# HydraBus_1_0_Shield_ESP_WROOM_32_v1_1_Re.net
KiCad netlist of a schematic drawn in EAGLE
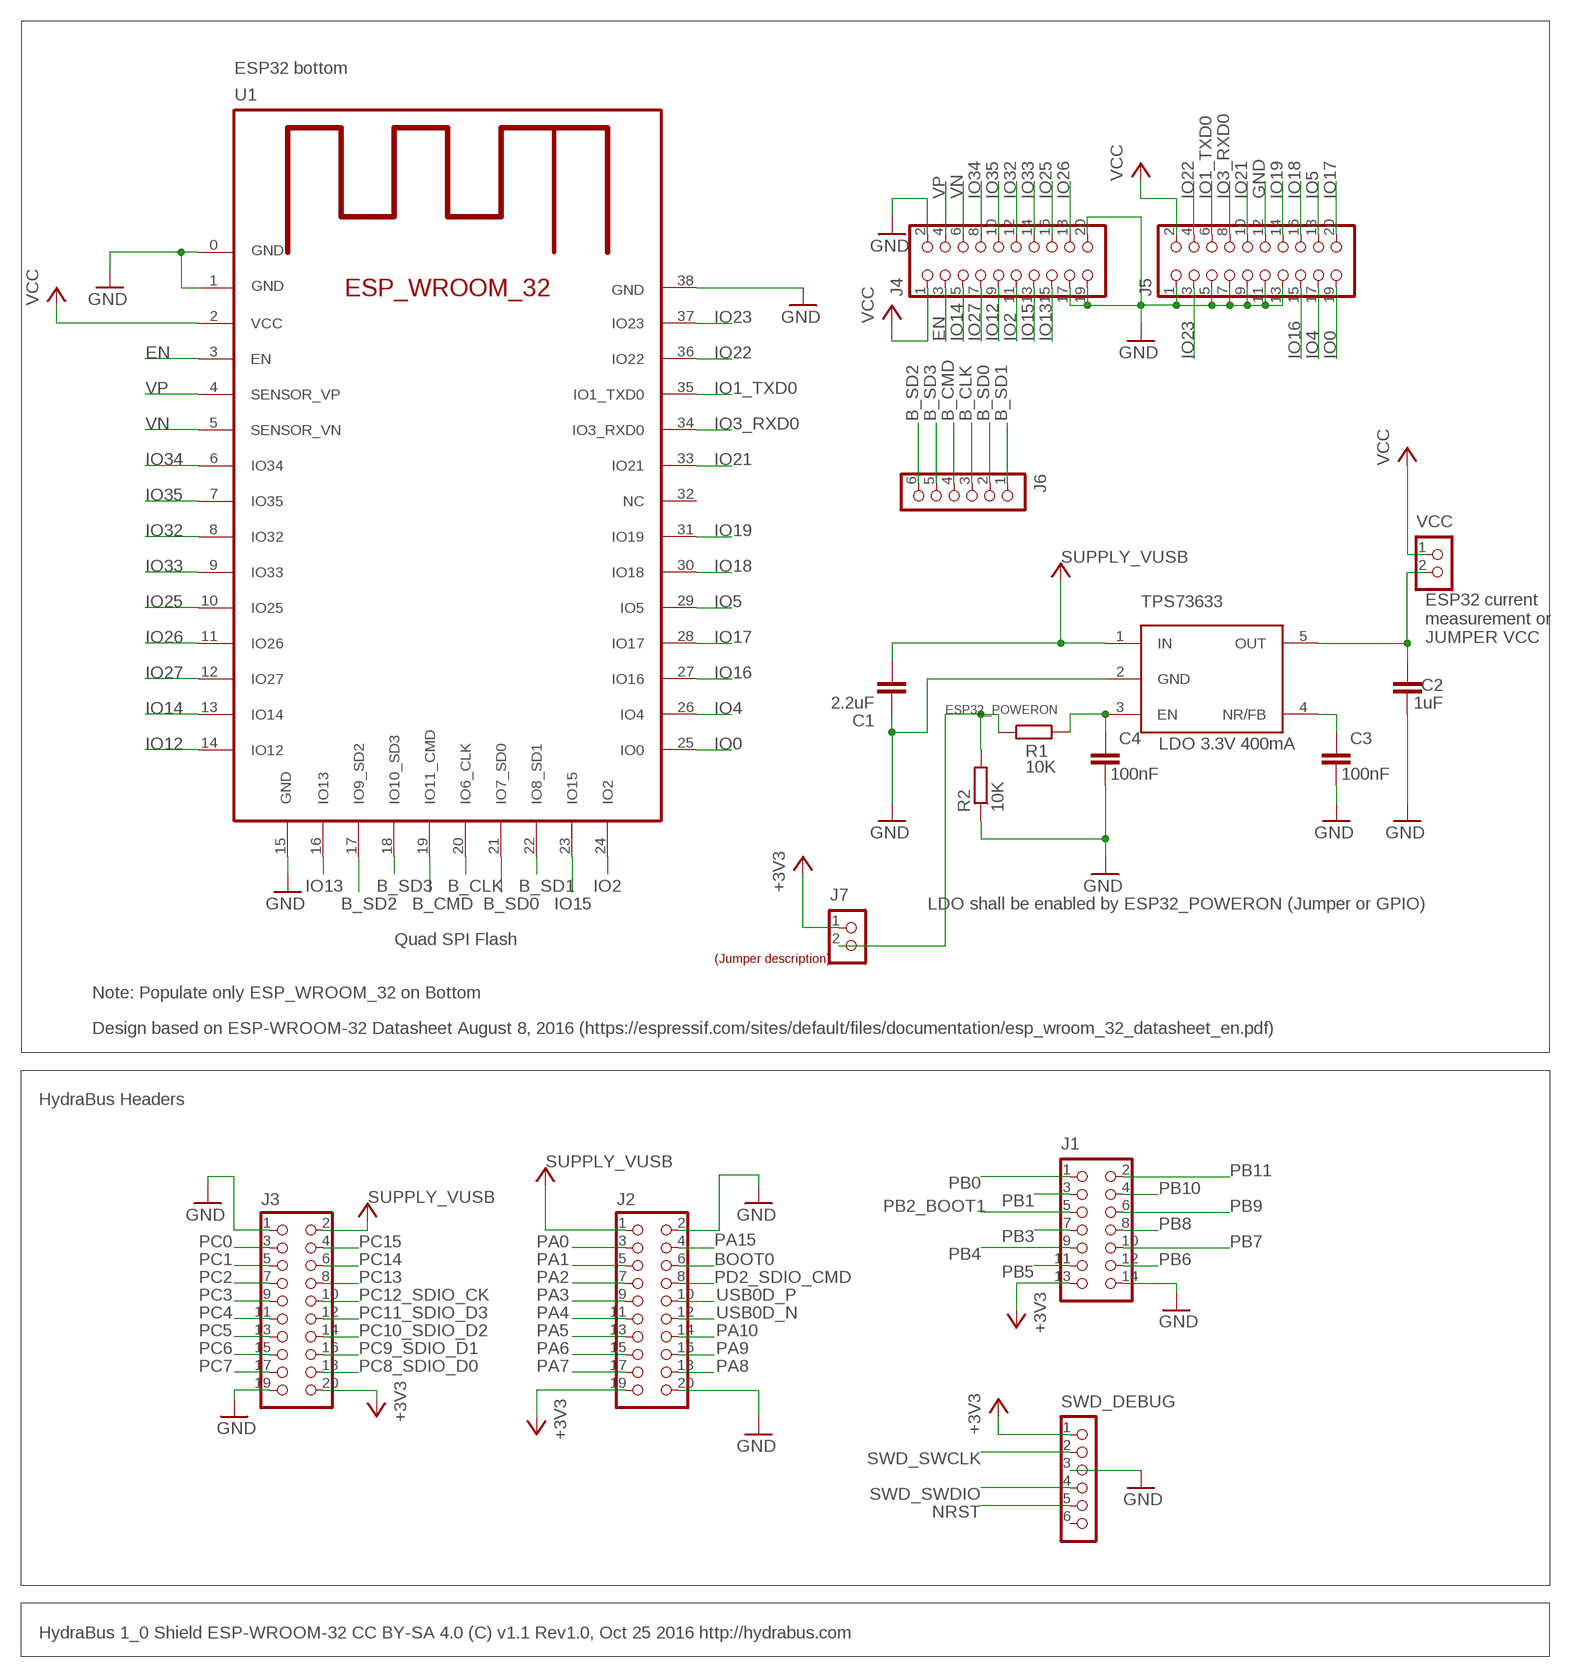
[diagram p0: schematic, sheet 1]

(export (version "E")
  (design (tool "Eeschema 10.0.6"))
  (components
    (comp (ref "C1")
      (value "2.2uF")
      (footprint "eagle-import:C603")
      (libsource (lib "eagle-import") (part "CAPACITOR_NPOL-0603"))
    )
    (comp (ref "C2")
      (value "1uF")
      (footprint "eagle-import:C603")
      (libsource (lib "eagle-import") (part "CAPACITOR_NPOL-0603"))
    )
    (comp (ref "C3")
      (value "100nF")
      (footprint "eagle-import:C603")
      (libsource (lib "eagle-import") (part "CAPACITOR_NPOL-0603"))
    )
    (comp (ref "C4")
      (value "100nF")
      (footprint "eagle-import:C603")
      (libsource (lib "eagle-import") (part "CAPACITOR_NPOL-0603"))
    )
    (comp (ref "J1")
      (value "HYDRABUS_SHIELD_CON_HEADER_2X07_BOTTOM")
      (footprint "eagle-import:HYDRABUS_SHIELD_M2X7_BOTTOM")
      (libsource (lib "eagle-import") (part "HYDRABUS_SHIELD_CON_HEADER_2X07_BOTTOM"))
    )
    (comp (ref "J2")
      (value "HYDRABUS_SHIELD_CON_HEADER_2X10_BOTTOM")
      (footprint "eagle-import:HYDRABUS_SHIELD_M2X10_BOTTOM")
      (libsource (lib "eagle-import") (part "HYDRABUS_SHIELD_CON_HEADER_2X10_BOTTOM"))
    )
    (comp (ref "J3")
      (value "HYDRABUS_SHIELD_CON_HEADER_2X10_BOTTOM")
      (footprint "eagle-import:HYDRABUS_SHIELD_M2X10_BOTTOM")
      (libsource (lib "eagle-import") (part "HYDRABUS_SHIELD_CON_HEADER_2X10_BOTTOM"))
    )
    (comp (ref "J4")
      (value "HYDRABUS_SHIELD_CON_HEADER_2X10")
      (footprint "eagle-import:HYDRABUS_SHIELD_M2X10")
      (libsource (lib "eagle-import") (part "HYDRABUS_SHIELD_CON_HEADER_2X10"))
    )
    (comp (ref "J5")
      (value "HYDRABUS_SHIELD_CON_HEADER_2X10")
      (footprint "eagle-import:HYDRABUS_SHIELD_M2X10")
      (libsource (lib "eagle-import") (part "HYDRABUS_SHIELD_CON_HEADER_2X10"))
    )
    (comp (ref "J6")
      (value "HYDRABUS_SHIELD_CON_HEADER_1X06")
      (footprint "eagle-import:HYDRABUS_SHIELD_M1X6")
      (libsource (lib "eagle-import") (part "HYDRABUS_SHIELD_CON_HEADER_1X06"))
    )
    (comp (ref "J7")
      (value "CON_HEADER_1X02-PTH")
      (footprint "eagle-import:M1X2")
      (libsource (lib "eagle-import") (part "CON_HEADER_1X02-PTH"))
    )
    (comp (ref "R1")
      (value "10K")
      (footprint "eagle-import:R603")
      (libsource (lib "eagle-import") (part "RESISTOR-0603"))
    )
    (comp (ref "R2")
      (value "10K")
      (footprint "eagle-import:R603")
      (libsource (lib "eagle-import") (part "RESISTOR-0603"))
    )
    (comp (ref "SWD_DEBUG")
      (value "HYDRABUS_SHIELD_CON_HEADER_1X06_BOTTOM")
      (footprint "eagle-import:HYDRABUS_SHIELD_M1X6_BOTTOM")
      (libsource (lib "eagle-import") (part "HYDRABUS_SHIELD_CON_HEADER_1X06_BOTTOM"))
    )
    (comp (ref "U$1")
      (value "LABEL_JUMPER_1X2")
      (footprint "eagle-import:JUMP2_DESC")
      (libsource (lib "eagle-import") (part "LABEL_JUMPER_1X2"))
    )
    (comp (ref "U1")
      (value "ESP_WROOM_32")
      (footprint "eagle-import:ESP_WROOM_32")
      (libsource (lib "eagle-import") (part "ESP_WROOM_32"))
    )
    (comp (ref "U2")
      (value "TPS73633")
      (footprint "eagle-import:SOT23-5L")
      (libsource (lib "eagle-import") (part "TPS73633"))
    )
    (comp (ref "VCC")
      (value "CON_HEADER_1X02-PTH")
      (footprint "eagle-import:M1X2")
      (libsource (lib "eagle-import") (part "CON_HEADER_1X02-PTH"))
    )
  )
  (nets
    (net (code "1") (name "+3V3") (class "Default")
      (node (ref "J1") (pin "13") (pinfunction "13_13") (pintype "passive"))
      (node (ref "J2") (pin "19") (pinfunction "19_19") (pintype "passive"))
      (node (ref "J3") (pin "20") (pinfunction "20_20") (pintype "passive"))
      (node (ref "J7") (pin "1") (pinfunction "1_1") (pintype "passive"))
      (node (ref "SWD_DEBUG") (pin "1") (pinfunction "1_1") (pintype "bidirectional"))
    )
    (net (code "2") (name "/BOOT0") (class "Default")
      (node (ref "J2") (pin "6") (pinfunction "6_6") (pintype "passive"))
    )
    (net (code "3") (name "/B_CLK") (class "Default")
      (node (ref "J6") (pin "3") (pinfunction "3_3") (pintype "passive"))
      (node (ref "U1") (pin "20") (pinfunction "IO6_CLK_20") (pintype "bidirectional"))
    )
    (net (code "4") (name "/B_CMD") (class "Default")
      (node (ref "J6") (pin "4") (pinfunction "4_4") (pintype "passive"))
      (node (ref "U1") (pin "19") (pinfunction "IO11_CMD_19") (pintype "bidirectional"))
    )
    (net (code "5") (name "/B_SD0") (class "Default")
      (node (ref "J6") (pin "2") (pinfunction "2_2") (pintype "bidirectional"))
      (node (ref "U1") (pin "21") (pinfunction "IO7_SD0_21") (pintype "bidirectional"))
    )
    (net (code "6") (name "/B_SD1") (class "Default")
      (node (ref "J6") (pin "1") (pinfunction "1_1") (pintype "bidirectional"))
      (node (ref "U1") (pin "22") (pinfunction "IO8_SD1_22") (pintype "bidirectional"))
    )
    (net (code "7") (name "/B_SD2") (class "Default")
      (node (ref "J6") (pin "6") (pinfunction "6_6") (pintype "passive"))
      (node (ref "U1") (pin "17") (pinfunction "IO9_SD2_17") (pintype "bidirectional"))
    )
    (net (code "8") (name "/B_SD3") (class "Default")
      (node (ref "J6") (pin "5") (pinfunction "5_5") (pintype "passive"))
      (node (ref "U1") (pin "18") (pinfunction "IO10_SD3_18") (pintype "bidirectional"))
    )
    (net (code "9") (name "/EN") (class "Default")
      (node (ref "J4") (pin "3") (pinfunction "3_3") (pintype "passive"))
      (node (ref "U1") (pin "3") (pinfunction "EN_3") (pintype "bidirectional"))
    )
    (net (code "10") (name "/ESP32_POWERON") (class "Default")
      (node (ref "J7") (pin "2") (pinfunction "2_2") (pintype "passive"))
      (node (ref "R1") (pin "1") (pinfunction "1_1") (pintype "passive"))
      (node (ref "R2") (pin "2") (pinfunction "2_2") (pintype "passive"))
    )
    (net (code "11") (name "/IO0") (class "Default")
      (node (ref "J5") (pin "19") (pinfunction "19_19") (pintype "passive"))
      (node (ref "U1") (pin "25") (pinfunction "IO0_25") (pintype "bidirectional"))
    )
    (net (code "12") (name "/IO1_TXD0") (class "Default")
      (node (ref "J5") (pin "6") (pinfunction "6_6") (pintype "passive"))
      (node (ref "U1") (pin "35") (pinfunction "IO1_TXD0_35") (pintype "bidirectional"))
    )
    (net (code "13") (name "/IO2") (class "Default")
      (node (ref "J4") (pin "11") (pinfunction "11_11") (pintype "passive"))
      (node (ref "U1") (pin "24") (pinfunction "IO2_24") (pintype "bidirectional"))
    )
    (net (code "14") (name "/IO3_RXD0") (class "Default")
      (node (ref "J5") (pin "8") (pinfunction "8_8") (pintype "passive"))
      (node (ref "U1") (pin "34") (pinfunction "IO3_RXD0_34") (pintype "bidirectional"))
    )
    (net (code "15") (name "/IO4") (class "Default")
      (node (ref "J5") (pin "17") (pinfunction "17_17") (pintype "passive"))
      (node (ref "U1") (pin "26") (pinfunction "IO4_26") (pintype "bidirectional"))
    )
    (net (code "16") (name "/IO5") (class "Default")
      (node (ref "J5") (pin "18") (pinfunction "18_18") (pintype "passive"))
      (node (ref "U1") (pin "29") (pinfunction "IO5_29") (pintype "bidirectional"))
    )
    (net (code "17") (name "/IO12") (class "Default")
      (node (ref "J4") (pin "9") (pinfunction "9_9") (pintype "passive"))
      (node (ref "U1") (pin "14") (pinfunction "IO12_14") (pintype "bidirectional"))
    )
    (net (code "18") (name "/IO13") (class "Default")
      (node (ref "J4") (pin "15") (pinfunction "15_15") (pintype "passive"))
      (node (ref "U1") (pin "16") (pinfunction "IO13_16") (pintype "bidirectional"))
    )
    (net (code "19") (name "/IO14") (class "Default")
      (node (ref "J4") (pin "5") (pinfunction "5_5") (pintype "passive"))
      (node (ref "U1") (pin "13") (pinfunction "IO14_13") (pintype "bidirectional"))
    )
    (net (code "20") (name "/IO15") (class "Default")
      (node (ref "J4") (pin "13") (pinfunction "13_13") (pintype "passive"))
      (node (ref "U1") (pin "23") (pinfunction "IO15_23") (pintype "bidirectional"))
    )
    (net (code "21") (name "/IO16") (class "Default")
      (node (ref "J5") (pin "15") (pinfunction "15_15") (pintype "passive"))
      (node (ref "U1") (pin "27") (pinfunction "IO16_27") (pintype "bidirectional"))
    )
    (net (code "22") (name "/IO17") (class "Default")
      (node (ref "J5") (pin "20") (pinfunction "20_20") (pintype "passive"))
      (node (ref "U1") (pin "28") (pinfunction "IO17_28") (pintype "bidirectional"))
    )
    (net (code "23") (name "/IO18") (class "Default")
      (node (ref "J5") (pin "16") (pinfunction "16_16") (pintype "passive"))
      (node (ref "U1") (pin "30") (pinfunction "IO18_30") (pintype "bidirectional"))
    )
    (net (code "24") (name "/IO19") (class "Default")
      (node (ref "J5") (pin "14") (pinfunction "14_14") (pintype "passive"))
      (node (ref "U1") (pin "31") (pinfunction "IO19_31") (pintype "bidirectional"))
    )
    (net (code "25") (name "/IO21") (class "Default")
      (node (ref "J5") (pin "10") (pinfunction "10_10") (pintype "passive"))
      (node (ref "U1") (pin "33") (pinfunction "IO21_33") (pintype "bidirectional"))
    )
    (net (code "26") (name "/IO22") (class "Default")
      (node (ref "J5") (pin "4") (pinfunction "4_4") (pintype "passive"))
      (node (ref "U1") (pin "36") (pinfunction "IO22_36") (pintype "bidirectional"))
    )
    (net (code "27") (name "/IO23") (class "Default")
      (node (ref "J5") (pin "3") (pinfunction "3_3") (pintype "passive"))
      (node (ref "U1") (pin "37") (pinfunction "IO23_37") (pintype "bidirectional"))
    )
    (net (code "28") (name "/IO25") (class "Default")
      (node (ref "J4") (pin "16") (pinfunction "16_16") (pintype "passive"))
      (node (ref "U1") (pin "10") (pinfunction "IO25_10") (pintype "bidirectional"))
    )
    (net (code "29") (name "/IO26") (class "Default")
      (node (ref "J4") (pin "18") (pinfunction "18_18") (pintype "passive"))
      (node (ref "U1") (pin "11") (pinfunction "IO26_11") (pintype "bidirectional"))
    )
    (net (code "30") (name "/IO27") (class "Default")
      (node (ref "J4") (pin "7") (pinfunction "7_7") (pintype "passive"))
      (node (ref "U1") (pin "12") (pinfunction "IO27_12") (pintype "bidirectional"))
    )
    (net (code "31") (name "/IO32") (class "Default")
      (node (ref "J4") (pin "12") (pinfunction "12_12") (pintype "passive"))
      (node (ref "U1") (pin "8") (pinfunction "IO32_8") (pintype "bidirectional"))
    )
    (net (code "32") (name "/IO33") (class "Default")
      (node (ref "J4") (pin "14") (pinfunction "14_14") (pintype "passive"))
      (node (ref "U1") (pin "9") (pinfunction "IO33_9") (pintype "bidirectional"))
    )
    (net (code "33") (name "/IO34") (class "Default")
      (node (ref "J4") (pin "8") (pinfunction "8_8") (pintype "passive"))
      (node (ref "U1") (pin "6") (pinfunction "IO34_6") (pintype "bidirectional"))
    )
    (net (code "34") (name "/IO35") (class "Default")
      (node (ref "J4") (pin "10") (pinfunction "10_10") (pintype "passive"))
      (node (ref "U1") (pin "7") (pinfunction "IO35_7") (pintype "bidirectional"))
    )
    (net (code "35") (name "/NRST") (class "Default")
      (node (ref "SWD_DEBUG") (pin "5") (pinfunction "5_5") (pintype "passive"))
    )
    (net (code "36") (name "/PA0") (class "Default")
      (node (ref "J2") (pin "3") (pinfunction "3_3") (pintype "passive"))
    )
    (net (code "37") (name "/PA1") (class "Default")
      (node (ref "J2") (pin "5") (pinfunction "5_5") (pintype "passive"))
    )
    (net (code "38") (name "/PA2") (class "Default")
      (node (ref "J2") (pin "7") (pinfunction "7_7") (pintype "passive"))
    )
    (net (code "39") (name "/PA3") (class "Default")
      (node (ref "J2") (pin "9") (pinfunction "9_9") (pintype "passive"))
    )
    (net (code "40") (name "/PA4") (class "Default")
      (node (ref "J2") (pin "11") (pinfunction "11_11") (pintype "passive"))
    )
    (net (code "41") (name "/PA5") (class "Default")
      (node (ref "J2") (pin "13") (pinfunction "13_13") (pintype "passive"))
    )
    (net (code "42") (name "/PA6") (class "Default")
      (node (ref "J2") (pin "15") (pinfunction "15_15") (pintype "passive"))
    )
    (net (code "43") (name "/PA7") (class "Default")
      (node (ref "J2") (pin "17") (pinfunction "17_17") (pintype "passive"))
    )
    (net (code "44") (name "/PA8") (class "Default")
      (node (ref "J2") (pin "18") (pinfunction "18_18") (pintype "passive"))
    )
    (net (code "45") (name "/PA9") (class "Default")
      (node (ref "J2") (pin "16") (pinfunction "16_16") (pintype "passive"))
    )
    (net (code "46") (name "/PA10") (class "Default")
      (node (ref "J2") (pin "14") (pinfunction "14_14") (pintype "passive"))
    )
    (net (code "47") (name "/PA15") (class "Default")
      (node (ref "J2") (pin "4") (pinfunction "4_4") (pintype "passive"))
    )
    (net (code "48") (name "/PB0") (class "Default")
      (node (ref "J1") (pin "1") (pinfunction "1_1") (pintype "passive"))
    )
    (net (code "49") (name "/PB1") (class "Default")
      (node (ref "J1") (pin "3") (pinfunction "3_3") (pintype "passive"))
    )
    (net (code "50") (name "/PB2_BOOT1") (class "Default")
      (node (ref "J1") (pin "5") (pinfunction "5_5") (pintype "passive"))
    )
    (net (code "51") (name "/PB3") (class "Default")
      (node (ref "J1") (pin "7") (pinfunction "7_7") (pintype "passive"))
    )
    (net (code "52") (name "/PB4") (class "Default")
      (node (ref "J1") (pin "9") (pinfunction "9_9") (pintype "passive"))
    )
    (net (code "53") (name "/PB5") (class "Default")
      (node (ref "J1") (pin "11") (pinfunction "11_11") (pintype "passive"))
    )
    (net (code "54") (name "/PB6") (class "Default")
      (node (ref "J1") (pin "12") (pinfunction "12_12") (pintype "passive"))
    )
    (net (code "55") (name "/PB7") (class "Default")
      (node (ref "J1") (pin "10") (pinfunction "10_10") (pintype "passive"))
    )
    (net (code "56") (name "/PB8") (class "Default")
      (node (ref "J1") (pin "8") (pinfunction "8_8") (pintype "passive"))
    )
    (net (code "57") (name "/PB9") (class "Default")
      (node (ref "J1") (pin "6") (pinfunction "6_6") (pintype "passive"))
    )
    (net (code "58") (name "/PB10") (class "Default")
      (node (ref "J1") (pin "4") (pinfunction "4_4") (pintype "passive"))
    )
    (net (code "59") (name "/PB11") (class "Default")
      (node (ref "J1") (pin "2") (pinfunction "2_2") (pintype "passive"))
    )
    (net (code "60") (name "/PC0") (class "Default")
      (node (ref "J3") (pin "3") (pinfunction "3_3") (pintype "passive"))
    )
    (net (code "61") (name "/PC1") (class "Default")
      (node (ref "J3") (pin "5") (pinfunction "5_5") (pintype "passive"))
    )
    (net (code "62") (name "/PC2") (class "Default")
      (node (ref "J3") (pin "7") (pinfunction "7_7") (pintype "passive"))
    )
    (net (code "63") (name "/PC3") (class "Default")
      (node (ref "J3") (pin "9") (pinfunction "9_9") (pintype "passive"))
    )
    (net (code "64") (name "/PC4") (class "Default")
      (node (ref "J3") (pin "11") (pinfunction "11_11") (pintype "passive"))
    )
    (net (code "65") (name "/PC5") (class "Default")
      (node (ref "J3") (pin "13") (pinfunction "13_13") (pintype "passive"))
    )
    (net (code "66") (name "/PC6") (class "Default")
      (node (ref "J3") (pin "15") (pinfunction "15_15") (pintype "passive"))
    )
    (net (code "67") (name "/PC7") (class "Default")
      (node (ref "J3") (pin "17") (pinfunction "17_17") (pintype "passive"))
    )
    (net (code "68") (name "/PC8_SDIO_D0") (class "Default")
      (node (ref "J3") (pin "18") (pinfunction "18_18") (pintype "passive"))
    )
    (net (code "69") (name "/PC9_SDIO_D1") (class "Default")
      (node (ref "J3") (pin "16") (pinfunction "16_16") (pintype "passive"))
    )
    (net (code "70") (name "/PC10_SDIO_D2") (class "Default")
      (node (ref "J3") (pin "14") (pinfunction "14_14") (pintype "passive"))
    )
    (net (code "71") (name "/PC11_SDIO_D3") (class "Default")
      (node (ref "J3") (pin "12") (pinfunction "12_12") (pintype "passive"))
    )
    (net (code "72") (name "/PC12_SDIO_CK") (class "Default")
      (node (ref "J3") (pin "10") (pinfunction "10_10") (pintype "passive"))
    )
    (net (code "73") (name "/PC13") (class "Default")
      (node (ref "J3") (pin "8") (pinfunction "8_8") (pintype "passive"))
    )
    (net (code "74") (name "/PC14") (class "Default")
      (node (ref "J3") (pin "6") (pinfunction "6_6") (pintype "passive"))
    )
    (net (code "75") (name "/PC15") (class "Default")
      (node (ref "J3") (pin "4") (pinfunction "4_4") (pintype "passive"))
    )
    (net (code "76") (name "/PD2_SDIO_CMD") (class "Default")
      (node (ref "J2") (pin "8") (pinfunction "8_8") (pintype "passive"))
    )
    (net (code "77") (name "/SWD_SWCLK") (class "Default")
      (node (ref "SWD_DEBUG") (pin "2") (pinfunction "2_2") (pintype "bidirectional"))
    )
    (net (code "78") (name "/SWD_SWDIO") (class "Default")
      (node (ref "SWD_DEBUG") (pin "4") (pinfunction "4_4") (pintype "passive"))
    )
    (net (code "79") (name "/USB0D_N") (class "Default")
      (node (ref "J2") (pin "12") (pinfunction "12_12") (pintype "passive"))
    )
    (net (code "80") (name "/USB0D_P") (class "Default")
      (node (ref "J2") (pin "10") (pinfunction "10_10") (pintype "passive"))
    )
    (net (code "81") (name "/VN") (class "Default")
      (node (ref "J4") (pin "6") (pinfunction "6_6") (pintype "passive"))
      (node (ref "U1") (pin "5") (pinfunction "SENSOR_VN_5") (pintype "bidirectional"))
    )
    (net (code "82") (name "/VP") (class "Default")
      (node (ref "J4") (pin "4") (pinfunction "4_4") (pintype "passive"))
      (node (ref "U1") (pin "4") (pinfunction "SENSOR_VP_4") (pintype "bidirectional"))
    )
    (net (code "83") (name "GND") (class "Default")
      (node (ref "C1") (pin "1") (pinfunction "1_1") (pintype "passive"))
      (node (ref "C2") (pin "1") (pinfunction "1_1") (pintype "passive"))
      (node (ref "C3") (pin "1") (pinfunction "1_1") (pintype "passive"))
      (node (ref "C4") (pin "1") (pinfunction "1_1") (pintype "passive"))
      (node (ref "J1") (pin "14") (pinfunction "14_14") (pintype "passive"))
      (node (ref "J2") (pin "2") (pinfunction "2_2") (pintype "passive"))
      (node (ref "J2") (pin "20") (pinfunction "20_20") (pintype "passive"))
      (node (ref "J3") (pin "1") (pinfunction "1_1") (pintype "passive"))
      (node (ref "J3") (pin "19") (pinfunction "19_19") (pintype "passive"))
      (node (ref "J4") (pin "17") (pinfunction "17_17") (pintype "passive"))
      (node (ref "J4") (pin "19") (pinfunction "19_19") (pintype "passive"))
      (node (ref "J4") (pin "2") (pinfunction "2_2") (pintype "passive"))
      (node (ref "J4") (pin "20") (pinfunction "20_20") (pintype "passive"))
      (node (ref "J5") (pin "1") (pinfunction "1_1") (pintype "passive"))
      (node (ref "J5") (pin "11") (pinfunction "11_11") (pintype "passive"))
      (node (ref "J5") (pin "12") (pinfunction "12_12") (pintype "passive"))
      (node (ref "J5") (pin "13") (pinfunction "13_13") (pintype "passive"))
      (node (ref "J5") (pin "5") (pinfunction "5_5") (pintype "passive"))
      (node (ref "J5") (pin "7") (pinfunction "7_7") (pintype "passive"))
      (node (ref "J5") (pin "9") (pinfunction "9_9") (pintype "passive"))
      (node (ref "R2") (pin "1") (pinfunction "1_1") (pintype "passive"))
      (node (ref "SWD_DEBUG") (pin "3") (pinfunction "3_3") (pintype "passive"))
      (node (ref "U1") (pin "0") (pinfunction "GND_0") (pintype "power_in"))
      (node (ref "U1") (pin "1") (pinfunction "GND_1") (pintype "power_in"))
      (node (ref "U1") (pin "15") (pinfunction "GND_15") (pintype "power_in"))
      (node (ref "U1") (pin "38") (pinfunction "GND_38") (pintype "power_in"))
      (node (ref "U2") (pin "2") (pinfunction "GND_2") (pintype "bidirectional"))
    )
    (net (code "84") (name "Net-(U2-EN)") (class "Default")
      (node (ref "C4") (pin "2") (pinfunction "2_2") (pintype "passive"))
      (node (ref "R1") (pin "2") (pinfunction "2_2") (pintype "passive"))
      (node (ref "U2") (pin "3") (pinfunction "EN_3") (pintype "bidirectional"))
    )
    (net (code "85") (name "Net-(U2-NR{slash}FB)") (class "Default")
      (node (ref "C3") (pin "2") (pinfunction "2_2") (pintype "passive"))
      (node (ref "U2") (pin "4") (pinfunction "NR/FB_4") (pintype "bidirectional"))
    )
    (net (code "86") (name "Net-(U2-OUT)") (class "Default")
      (node (ref "C2") (pin "2") (pinfunction "2_2") (pintype "passive"))
      (node (ref "U2") (pin "5") (pinfunction "OUT_5") (pintype "bidirectional"))
      (node (ref "VCC") (pin "2") (pinfunction "2_2") (pintype "passive"))
    )
    (net (code "87") (name "SUPPLY_VUSB") (class "Default")
      (node (ref "C1") (pin "2") (pinfunction "2_2") (pintype "passive"))
      (node (ref "J2") (pin "1") (pinfunction "1_1") (pintype "passive"))
      (node (ref "J3") (pin "2") (pinfunction "2_2") (pintype "passive"))
      (node (ref "U2") (pin "1") (pinfunction "IN_1") (pintype "bidirectional"))
    )
    (net (code "88") (name "VCC") (class "Default")
      (node (ref "J4") (pin "1") (pinfunction "1_1") (pintype "passive"))
      (node (ref "J5") (pin "2") (pinfunction "2_2") (pintype "passive"))
      (node (ref "U1") (pin "2") (pinfunction "VCC_2") (pintype "power_in"))
      (node (ref "VCC") (pin "1") (pinfunction "1_1") (pintype "passive"))
    )
    (net (code "89") (name "unconnected-(SWD_DEBUG-Pad6)") (class "Default")
      (node (ref "SWD_DEBUG") (pin "6") (pinfunction "6_6") (pintype "passive"))
    )
    (net (code "90") (name "unconnected-(U1-NC-Pad32)") (class "Default")
      (node (ref "U1") (pin "32") (pinfunction "NC_32") (pintype "bidirectional"))
    )
  )
)
